# SIS_Hub.net
KiCad netlist of a schematic drawn in EAGLE
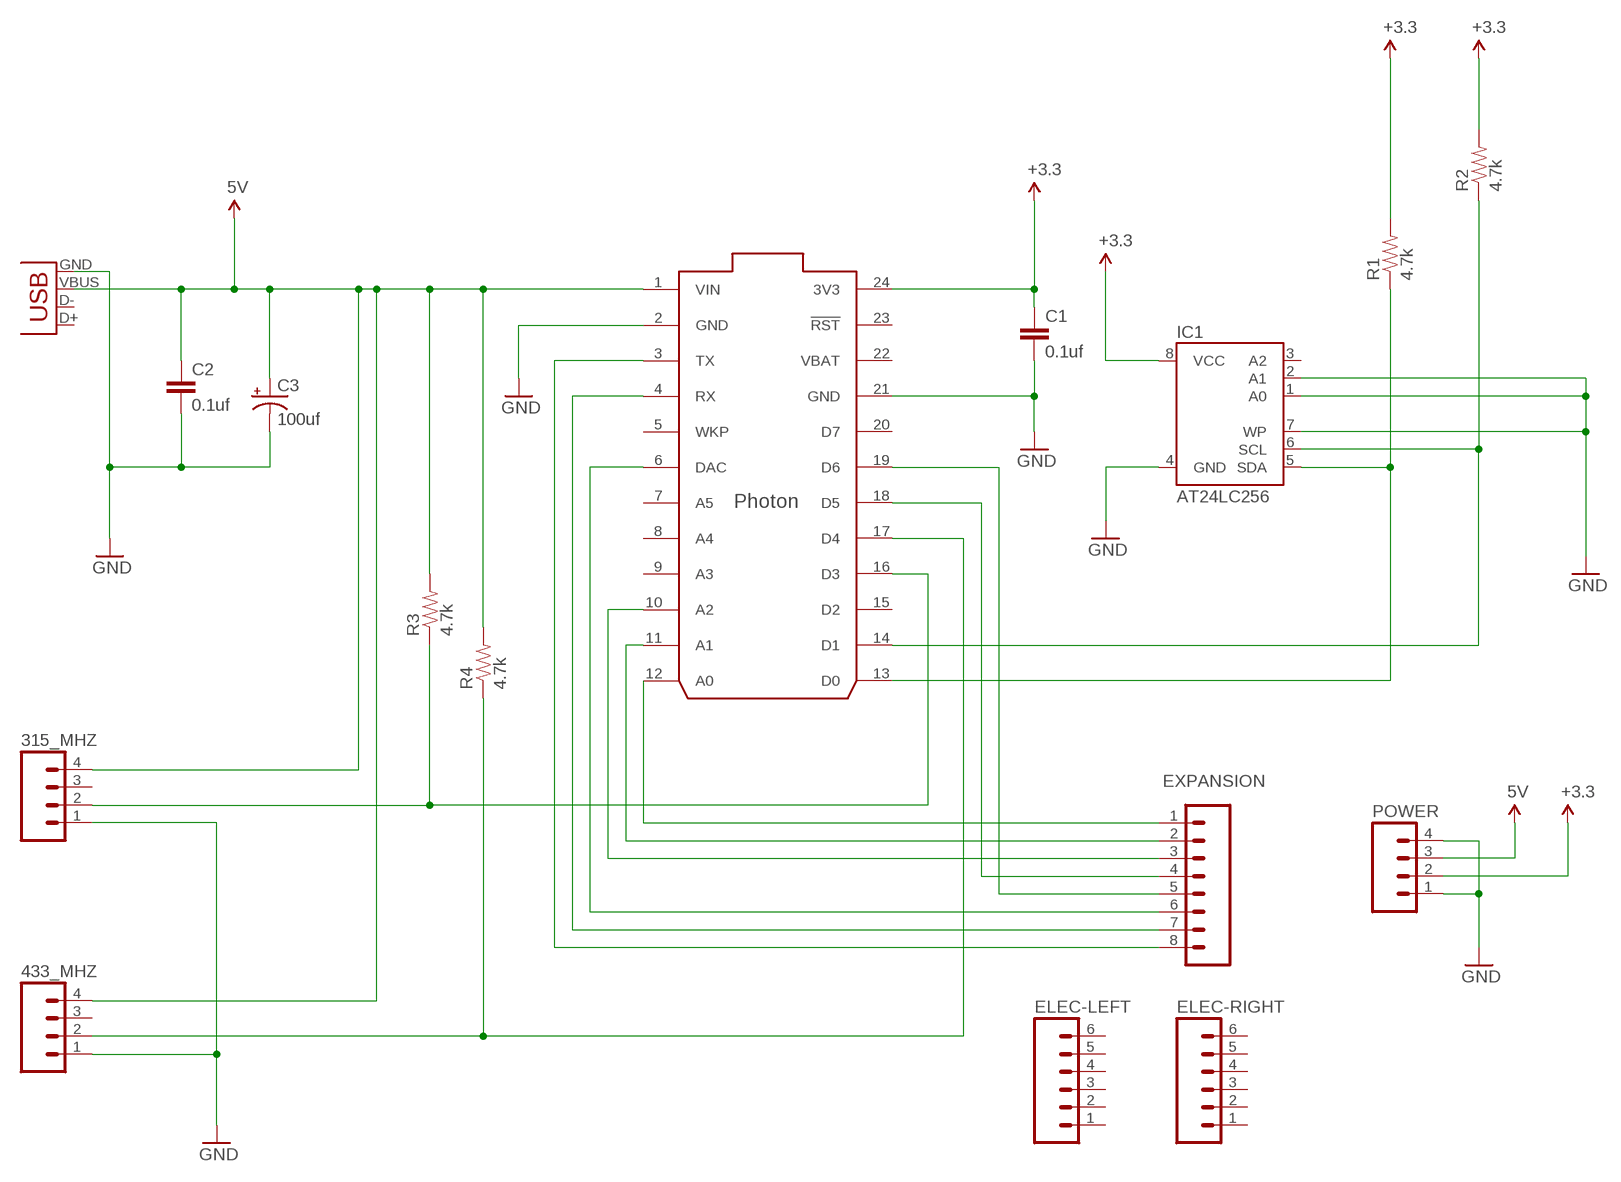
[diagram p0: schematic, sheet 1]

(export (version "E")
  (design (tool "Eeschema 10.0.6"))
  (components
    (comp (ref "315_MHZ")
      (value "M04PTH")
      (footprint "eagle-import:1X04")
      (libsource (lib "eagle-import") (part "M04PTH"))
    )
    (comp (ref "433_MHZ")
      (value "M04PTH")
      (footprint "eagle-import:1X04")
      (libsource (lib "eagle-import") (part "M04PTH"))
    )
    (comp (ref "C1")
      (value "0.1uf")
      (footprint "eagle-import:CAP-PTH-SMALL-KIT")
      (libsource (lib "eagle-import") (part "CAPKIT"))
    )
    (comp (ref "C2")
      (value "0.1uf")
      (footprint "eagle-import:CAP-PTH-SMALL-KIT")
      (libsource (lib "eagle-import") (part "CAPKIT"))
    )
    (comp (ref "C3")
      (value "100uf")
      (footprint "eagle-import:CPOL-RADIAL-100UF-25V")
      (libsource (lib "eagle-import") (part "100UF-25V-20%(PTH)"))
    )
    (comp (ref "ELEC-LEFT")
      (value "M06NO_SILK_FEMALE_PTH")
      (footprint "eagle-import:1X06_NO_SILK")
      (libsource (lib "eagle-import") (part "M06NO_SILK_FEMALE_PTH"))
    )
    (comp (ref "ELEC-RIGHT")
      (value "M06NO_SILK_FEMALE_PTH")
      (footprint "eagle-import:1X06_NO_SILK")
      (libsource (lib "eagle-import") (part "M06NO_SILK_FEMALE_PTH"))
    )
    (comp (ref "EXPANSION")
      (value "M08SILK_FEMALE_PTH")
      (footprint "eagle-import:1X08")
      (libsource (lib "eagle-import") (part "M08SILK_FEMALE_PTH"))
    )
    (comp (ref "IC1")
      (value "AT24LC256")
      (footprint "eagle-import:DIL08")
      (fields (field (name "MPN") "AT24C1024BW-SH-B"))
      (libsource (lib "eagle-import") (part "AT24CP"))
    )
    (comp (ref "JP1")
      (value "USB-B")
      (footprint "eagle-import:USB-B-PTH")
      (libsource (lib "eagle-import") (part "USBPTH"))
    )
    (comp (ref "POWER")
      (value "M04PTH")
      (footprint "eagle-import:1X04")
      (libsource (lib "eagle-import") (part "M04PTH"))
    )
    (comp (ref "R1")
      (value "4.7k")
      (footprint "eagle-import:AXIAL-0.4")
      (libsource (lib "eagle-import") (part "RESISTORPTH-1/4W"))
    )
    (comp (ref "R2")
      (value "4.7k")
      (footprint "eagle-import:AXIAL-0.4")
      (libsource (lib "eagle-import") (part "RESISTORPTH-1/4W"))
    )
    (comp (ref "R3")
      (value "4.7k")
      (footprint "eagle-import:AXIAL-0.4")
      (libsource (lib "eagle-import") (part "RESISTORPTH-1/4W"))
    )
    (comp (ref "R4")
      (value "4.7k")
      (footprint "eagle-import:AXIAL-0.4")
      (libsource (lib "eagle-import") (part "RESISTORPTH-1/4W"))
    )
    (comp (ref "U$1")
      (value "PHOTON_WITH_HEADERS")
      (footprint "eagle-import:PHOTON")
      (libsource (lib "eagle-import") (part "PHOTON_WITH_HEADERS"))
    )
  )
  (nets
    (net (code "1") (name "+3.3") (class "Default")
      (node (ref "C1") (pin "1") (pinfunction "1_1") (pintype "passive"))
      (node (ref "IC1") (pin "8") (pinfunction "VCC_8") (pintype "power_in"))
      (node (ref "POWER") (pin "2") (pinfunction "2_2") (pintype "passive"))
      (node (ref "R1") (pin "P$2") (pinfunction "2_P$2") (pintype "passive"))
      (node (ref "R2") (pin "P$2") (pinfunction "2_P$2") (pintype "passive"))
      (node (ref "U$1") (pin "24") (pinfunction "3V3_24") (pintype "power_in"))
    )
    (net (code "2") (name "/VBAT") (class "Default")
      (node (ref "U$1") (pin "22") (pinfunction "VBAT_22") (pintype "power_in"))
    )
    (net (code "3") (name "5V") (class "Default")
      (node (ref "315_MHZ") (pin "4") (pinfunction "4_4") (pintype "passive"))
      (node (ref "433_MHZ") (pin "4") (pinfunction "4_4") (pintype "passive"))
      (node (ref "C2") (pin "1") (pinfunction "1_1") (pintype "passive"))
      (node (ref "C3") (pin "1") (pinfunction "+_1") (pintype "passive"))
      (node (ref "JP1") (pin "VBUS") (pinfunction "VBUS_VBUS") (pintype "bidirectional"))
      (node (ref "POWER") (pin "3") (pinfunction "3_3") (pintype "passive"))
      (node (ref "R3") (pin "P$2") (pinfunction "2_P$2") (pintype "passive"))
      (node (ref "R4") (pin "P$2") (pinfunction "2_P$2") (pintype "passive"))
      (node (ref "U$1") (pin "1") (pinfunction "VIN_1") (pintype "power_in"))
    )
    (net (code "4") (name "GND") (class "Default")
      (node (ref "315_MHZ") (pin "1") (pinfunction "1_1") (pintype "passive"))
      (node (ref "433_MHZ") (pin "1") (pinfunction "1_1") (pintype "passive"))
      (node (ref "C1") (pin "2") (pinfunction "2_2") (pintype "passive"))
      (node (ref "C2") (pin "2") (pinfunction "2_2") (pintype "passive"))
      (node (ref "C3") (pin "2") (pinfunction "-_2") (pintype "passive"))
      (node (ref "IC1") (pin "1") (pinfunction "A0_1") (pintype "input"))
      (node (ref "IC1") (pin "2") (pinfunction "A1_2") (pintype "input"))
      (node (ref "IC1") (pin "4") (pinfunction "GND_4") (pintype "power_in"))
      (node (ref "IC1") (pin "7") (pinfunction "WP_7") (pintype "input"))
      (node (ref "JP1") (pin "GND") (pinfunction "GND_GND") (pintype "bidirectional"))
      (node (ref "POWER") (pin "1") (pinfunction "1_1") (pintype "passive"))
      (node (ref "POWER") (pin "4") (pinfunction "4_4") (pintype "passive"))
      (node (ref "U$1") (pin "2") (pinfunction "GND_2") (pintype "power_in"))
      (node (ref "U$1") (pin "21") (pinfunction "GND_21") (pintype "power_in"))
    )
    (net (code "5") (name "Net-(IC1-SCL)") (class "Default")
      (node (ref "IC1") (pin "6") (pinfunction "SCL_6") (pintype "bidirectional"))
      (node (ref "R2") (pin "P$1") (pinfunction "1_P$1") (pintype "passive"))
      (node (ref "U$1") (pin "14") (pinfunction "D1_14") (pintype "bidirectional"))
    )
    (net (code "6") (name "Net-(IC1-SDA)") (class "Default")
      (node (ref "IC1") (pin "5") (pinfunction "SDA_5") (pintype "bidirectional"))
      (node (ref "R1") (pin "P$1") (pinfunction "1_P$1") (pintype "passive"))
      (node (ref "U$1") (pin "13") (pinfunction "D0_13") (pintype "bidirectional"))
    )
    (net (code "7") (name "Net-(R3-1)") (class "Default")
      (node (ref "315_MHZ") (pin "2") (pinfunction "2_2") (pintype "passive"))
      (node (ref "R3") (pin "P$1") (pinfunction "1_P$1") (pintype "passive"))
      (node (ref "U$1") (pin "16") (pinfunction "D3_16") (pintype "bidirectional"))
    )
    (net (code "8") (name "Net-(R4-1)") (class "Default")
      (node (ref "433_MHZ") (pin "2") (pinfunction "2_2") (pintype "passive"))
      (node (ref "R4") (pin "P$1") (pinfunction "1_P$1") (pintype "passive"))
      (node (ref "U$1") (pin "17") (pinfunction "D4_17") (pintype "bidirectional"))
    )
    (net (code "9") (name "Net-(U$1-A0)") (class "Default")
      (node (ref "EXPANSION") (pin "1") (pinfunction "1_1") (pintype "passive"))
      (node (ref "U$1") (pin "12") (pinfunction "A0_12") (pintype "bidirectional"))
    )
    (net (code "10") (name "Net-(U$1-A1)") (class "Default")
      (node (ref "EXPANSION") (pin "2") (pinfunction "2_2") (pintype "passive"))
      (node (ref "U$1") (pin "11") (pinfunction "A1_11") (pintype "bidirectional"))
    )
    (net (code "11") (name "Net-(U$1-A2)") (class "Default")
      (node (ref "EXPANSION") (pin "3") (pinfunction "3_3") (pintype "passive"))
      (node (ref "U$1") (pin "10") (pinfunction "A2_10") (pintype "bidirectional"))
    )
    (net (code "12") (name "Net-(U$1-D5)") (class "Default")
      (node (ref "EXPANSION") (pin "4") (pinfunction "4_4") (pintype "passive"))
      (node (ref "U$1") (pin "18") (pinfunction "D5_18") (pintype "bidirectional"))
    )
    (net (code "13") (name "Net-(U$1-D6)") (class "Default")
      (node (ref "EXPANSION") (pin "5") (pinfunction "5_5") (pintype "passive"))
      (node (ref "U$1") (pin "19") (pinfunction "D6_19") (pintype "bidirectional"))
    )
    (net (code "14") (name "Net-(U$1-DAC)") (class "Default")
      (node (ref "EXPANSION") (pin "6") (pinfunction "6_6") (pintype "passive"))
      (node (ref "U$1") (pin "6") (pinfunction "DAC_6") (pintype "bidirectional"))
    )
    (net (code "15") (name "Net-(U$1-RX)") (class "Default")
      (node (ref "EXPANSION") (pin "7") (pinfunction "7_7") (pintype "passive"))
      (node (ref "U$1") (pin "4") (pinfunction "RX_4") (pintype "bidirectional"))
    )
    (net (code "16") (name "Net-(U$1-TX)") (class "Default")
      (node (ref "EXPANSION") (pin "8") (pinfunction "8_8") (pintype "passive"))
      (node (ref "U$1") (pin "3") (pinfunction "TX_3") (pintype "bidirectional"))
    )
    (net (code "17") (name "unconnected-(315_MHZ-Pad3)") (class "Default")
      (node (ref "315_MHZ") (pin "3") (pinfunction "3_3") (pintype "passive"))
    )
    (net (code "18") (name "unconnected-(433_MHZ-Pad3)") (class "Default")
      (node (ref "433_MHZ") (pin "3") (pinfunction "3_3") (pintype "passive"))
    )
    (net (code "19") (name "unconnected-(ELEC-LEFT-Pad1)") (class "Default")
      (node (ref "ELEC-LEFT") (pin "1") (pinfunction "1_1") (pintype "passive"))
    )
    (net (code "20") (name "unconnected-(ELEC-LEFT-Pad2)") (class "Default")
      (node (ref "ELEC-LEFT") (pin "2") (pinfunction "2_2") (pintype "passive"))
    )
    (net (code "21") (name "unconnected-(ELEC-LEFT-Pad3)") (class "Default")
      (node (ref "ELEC-LEFT") (pin "3") (pinfunction "3_3") (pintype "passive"))
    )
    (net (code "22") (name "unconnected-(ELEC-LEFT-Pad4)") (class "Default")
      (node (ref "ELEC-LEFT") (pin "4") (pinfunction "4_4") (pintype "passive"))
    )
    (net (code "23") (name "unconnected-(ELEC-LEFT-Pad5)") (class "Default")
      (node (ref "ELEC-LEFT") (pin "5") (pinfunction "5_5") (pintype "passive"))
    )
    (net (code "24") (name "unconnected-(ELEC-LEFT-Pad6)") (class "Default")
      (node (ref "ELEC-LEFT") (pin "6") (pinfunction "6_6") (pintype "passive"))
    )
    (net (code "25") (name "unconnected-(ELEC-RIGHT-Pad1)") (class "Default")
      (node (ref "ELEC-RIGHT") (pin "1") (pinfunction "1_1") (pintype "passive"))
    )
    (net (code "26") (name "unconnected-(ELEC-RIGHT-Pad2)") (class "Default")
      (node (ref "ELEC-RIGHT") (pin "2") (pinfunction "2_2") (pintype "passive"))
    )
    (net (code "27") (name "unconnected-(ELEC-RIGHT-Pad3)") (class "Default")
      (node (ref "ELEC-RIGHT") (pin "3") (pinfunction "3_3") (pintype "passive"))
    )
    (net (code "28") (name "unconnected-(ELEC-RIGHT-Pad4)") (class "Default")
      (node (ref "ELEC-RIGHT") (pin "4") (pinfunction "4_4") (pintype "passive"))
    )
    (net (code "29") (name "unconnected-(ELEC-RIGHT-Pad5)") (class "Default")
      (node (ref "ELEC-RIGHT") (pin "5") (pinfunction "5_5") (pintype "passive"))
    )
    (net (code "30") (name "unconnected-(ELEC-RIGHT-Pad6)") (class "Default")
      (node (ref "ELEC-RIGHT") (pin "6") (pinfunction "6_6") (pintype "passive"))
    )
    (net (code "31") (name "unconnected-(IC1-A2-Pad3)") (class "Default")
      (node (ref "IC1") (pin "3") (pinfunction "A2_3") (pintype "input"))
    )
    (net (code "32") (name "unconnected-(JP1-PadD+)") (class "Default")
      (node (ref "JP1") (pin "D+") (pinfunction "D+_D+") (pintype "bidirectional"))
    )
    (net (code "33") (name "unconnected-(JP1-PadD-)") (class "Default")
      (node (ref "JP1") (pin "D-") (pinfunction "D-_D-") (pintype "bidirectional"))
    )
    (net (code "34") (name "unconnected-(U$1-A3-Pad9)") (class "Default")
      (node (ref "U$1") (pin "9") (pinfunction "A3_9") (pintype "bidirectional"))
    )
    (net (code "35") (name "unconnected-(U$1-A4-Pad8)") (class "Default")
      (node (ref "U$1") (pin "8") (pinfunction "A4_8") (pintype "bidirectional"))
    )
    (net (code "36") (name "unconnected-(U$1-A5-Pad7)") (class "Default")
      (node (ref "U$1") (pin "7") (pinfunction "A5_7") (pintype "bidirectional"))
    )
    (net (code "37") (name "unconnected-(U$1-D2-Pad15)") (class "Default")
      (node (ref "U$1") (pin "15") (pinfunction "D2_15") (pintype "bidirectional"))
    )
    (net (code "38") (name "unconnected-(U$1-D7-Pad20)") (class "Default")
      (node (ref "U$1") (pin "20") (pinfunction "D7_20") (pintype "bidirectional"))
    )
    (net (code "39") (name "unconnected-(U$1-WKP-Pad5)") (class "Default")
      (node (ref "U$1") (pin "5") (pinfunction "WKP_5") (pintype "bidirectional"))
    )
    (net (code "40") (name "unconnected-(U$1-~{RST}-Pad23)") (class "Default")
      (node (ref "U$1") (pin "23") (pinfunction "~{RST}_23") (pintype "bidirectional"))
    )
  )
)
